# LTC-MTC_Filtering.net
KiCad netlist of a schematic drawn in Altium Designer
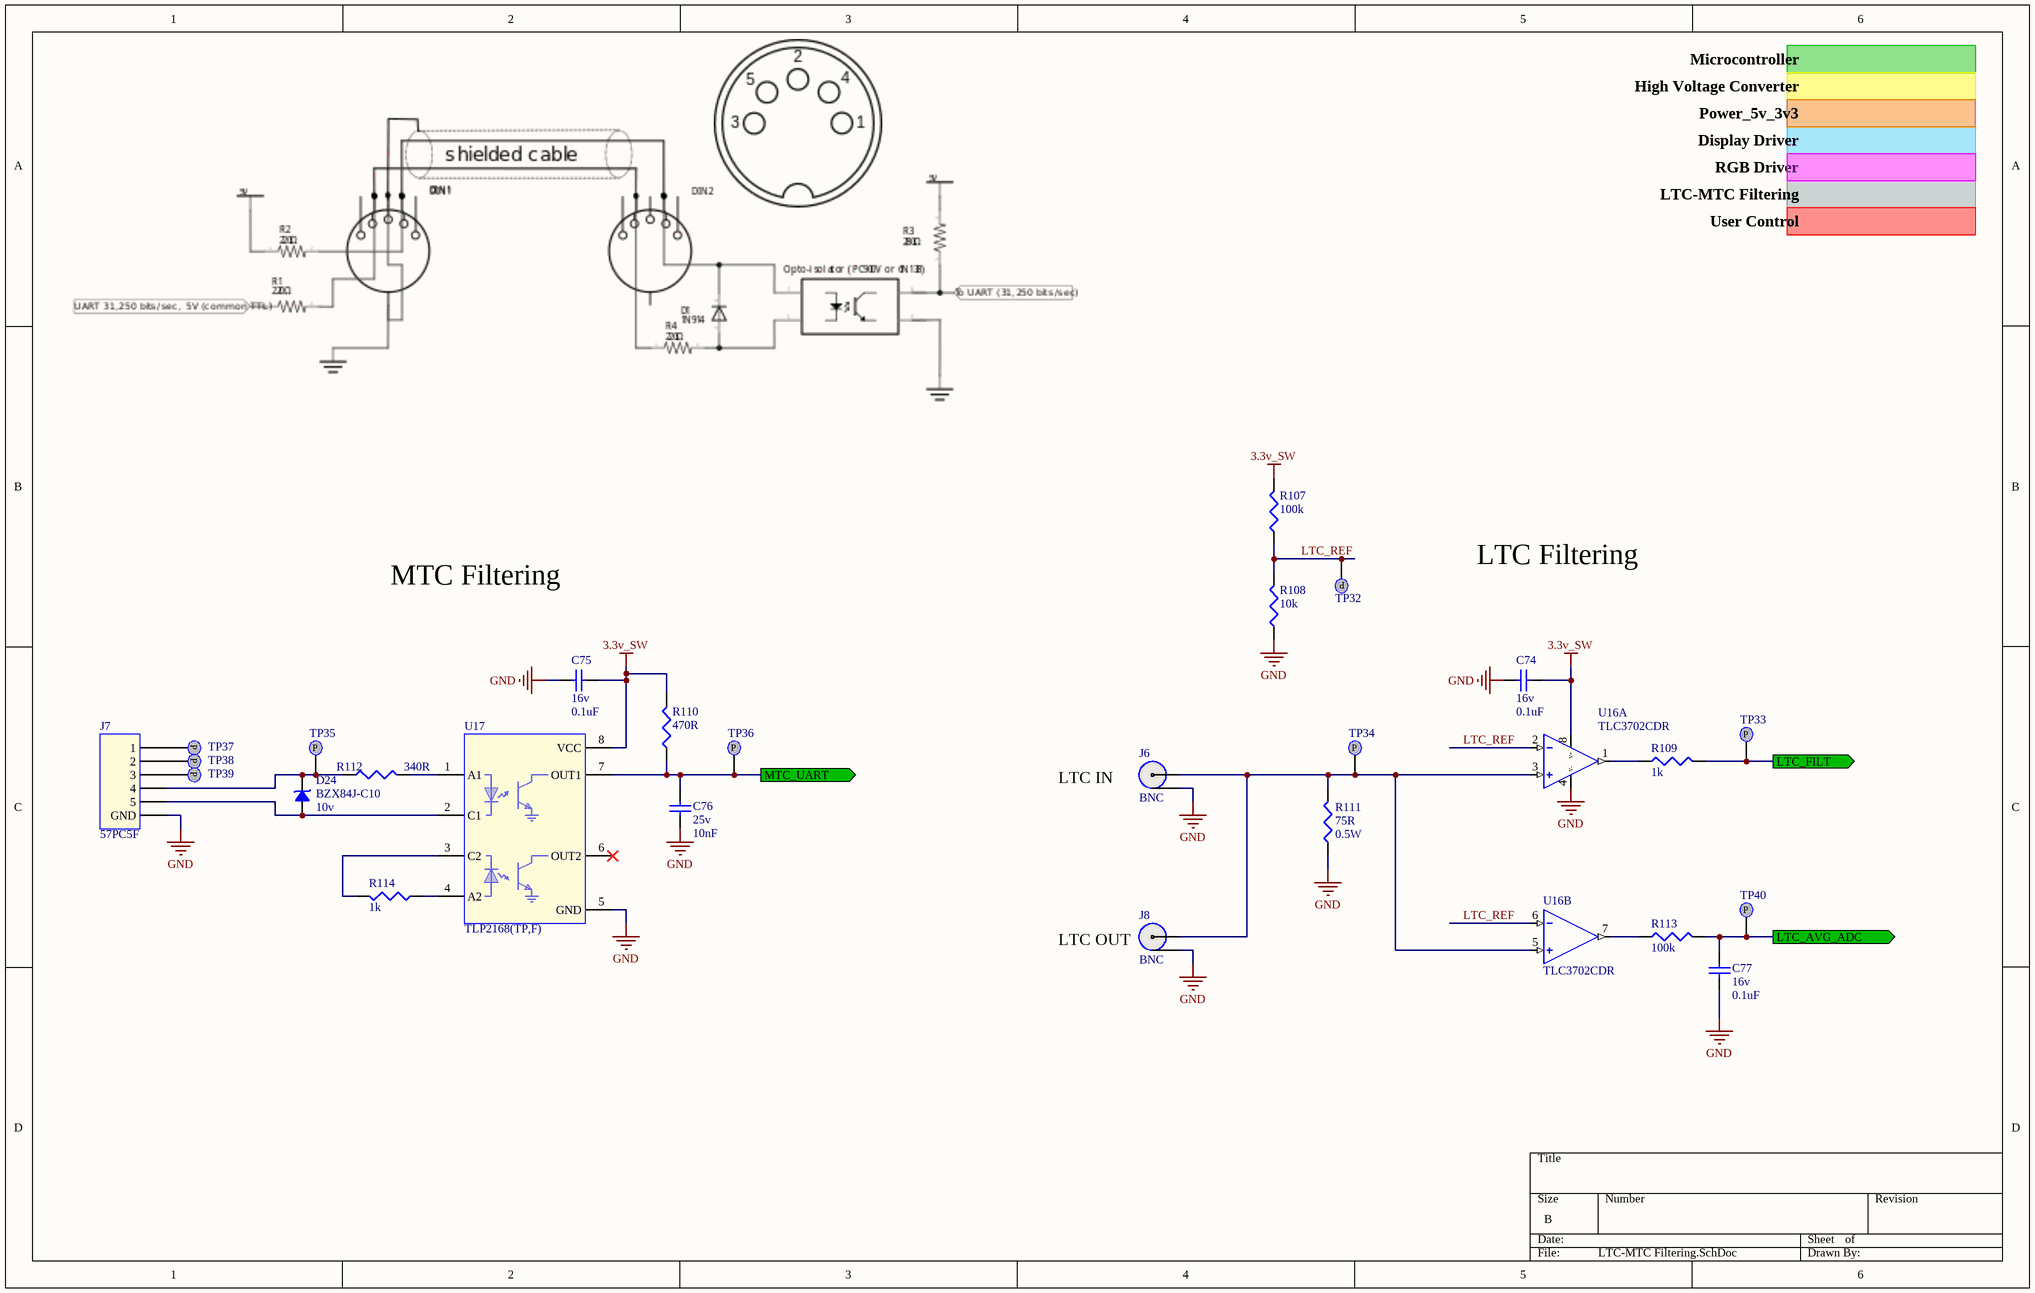
[diagram p0: LTC-MTC Filtering.SchDoc]

(export (version "E")
  (design (tool "Eeschema 10.0.6"))
  (components
    (comp (ref "C74")
      (value "0.1uF")
      (footprint "CAP0603R")
      (fields (field (name "MFG") "Vishay") (field (name "VOLTAGE") "16v"))
      (libsource (lib "Altium Library") (part "0.1uF 16v (0603)"))
    )
    (comp (ref "C75")
      (value "0.1uF")
      (footprint "CAP0603R")
      (fields (field (name "MFG") "Vishay") (field (name "VOLTAGE") "16v"))
      (libsource (lib "Altium Library") (part "0.1uF 16v (0603)"))
    )
    (comp (ref "C76")
      (value "10nF")
      (footprint "CAP0402R")
      (fields (field (name "TOLERANCE") "5%") (field (name "MFG") "Vishay") (field (name "VOLTAGE") "25v"))
      (libsource (lib "Altium Library") (part "10nF 25v (0402)"))
    )
    (comp (ref "C77")
      (value "0.1uF")
      (footprint "CAP0603R")
      (fields (field (name "MFG") "Vishay") (field (name "VOLTAGE") "16v"))
      (libsource (lib "Altium Library") (part "0.1uF 16v (0603)"))
    )
    (comp (ref "D24")
      (value "BZX84J-C10")
      (footprint "SOD-323 (SC-90)")
      (description "Zener, 10v, Single")
      (fields (field (name "MFG") "NXP") (field (name "OPER_VOLTAGE") "10v"))
      (libsource (lib "Altium Library") (part "BZX84J-C10"))
    )
    (comp (ref "J6")
      (value "BNC")
      (footprint "BNC Connector")
      (fields (field (name "MFG") "VITELEC"))
      (libsource (lib "Altium Library") (part "BNC Connector"))
    )
    (comp (ref "J7")
      (value "57PC5F")
      (footprint "57PC5F")
      (description "5-pin DIN Connector")
      (fields (field (name "MFG") "SWITCHCRAFT"))
      (libsource (lib "Altium Library") (part "57PC5F"))
    )
    (comp (ref "J8")
      (value "BNC")
      (footprint "BNC Connector")
      (fields (field (name "MFG") "VITELEC"))
      (libsource (lib "Altium Library") (part "BNC Connector"))
    )
    (comp (ref "R107")
      (value "100k")
      (footprint "RES0402R")
      (fields (field (name "TOLERANCE") "1%") (field (name "POWER") "63mW") (field (name "MFG") "Vishay"))
      (libsource (lib "Altium Library") (part "100k (0402)"))
    )
    (comp (ref "R108")
      (value "10k")
      (footprint "RES0402R")
      (fields (field (name "TOLERANCE") "1%") (field (name "POWER") "63mW") (field (name "MFG") "Vishay"))
      (libsource (lib "Altium Library") (part "10k (0402)"))
    )
    (comp (ref "R109")
      (value "1k")
      (footprint "RES0402R")
      (fields (field (name "TOLERANCE") "1%") (field (name "POWER") "63mW") (field (name "MFG") "Vishay"))
      (libsource (lib "Altium Library") (part "1k (0402)"))
    )
    (comp (ref "R110")
      (value "470R")
      (footprint "RES0603R")
      (fields (field (name "TOLERANCE") "1%") (field (name "POWER") "0.1W") (field (name "MFG") "Vishay"))
      (libsource (lib "Altium Library") (part "470R (0603)"))
    )
    (comp (ref "R111")
      (value "75R")
      (footprint "RES1210R")
      (fields (field (name "TOLERANCE") "1%") (field (name "POWER") "0.5W") (field (name "MFG") "Vishay"))
      (libsource (lib "Altium Library") (part "75R (1210)"))
    )
    (comp (ref "R112")
      (value "340R")
      (footprint "RES0603R")
      (fields (field (name "TOLERANCE") "1%") (field (name "POWER") "0.1W") (field (name "MFG") "Vishay"))
      (libsource (lib "Altium Library") (part "340R (0603)"))
    )
    (comp (ref "R113")
      (value "100k")
      (footprint "RES0402R")
      (fields (field (name "TOLERANCE") "1%") (field (name "POWER") "63mW") (field (name "MFG") "Vishay"))
      (libsource (lib "Altium Library") (part "100k (0402)"))
    )
    (comp (ref "R114")
      (value "1k")
      (footprint "RES0402R")
      (fields (field (name "TOLERANCE") "1%") (field (name "POWER") "63mW") (field (name "MFG") "Vishay"))
      (libsource (lib "Altium Library") (part "1k (0402)"))
    )
    (comp (ref "TP32")
      (value "NONE")
      (footprint "TESTPOINT - 1.5mm Round Pad")
      (description "1.5mm Testpoint")
      (libsource (lib "Altium Library") (part "Testpoint 1.5mm Pad"))
    )
    (comp (ref "TP33")
      (value "NONE")
      (footprint "TESTPOINT - 1.5mm Round Pad")
      (description "1.5mm Testpoint")
      (libsource (lib "Altium Library") (part "Testpoint 1.5mm Pad"))
    )
    (comp (ref "TP34")
      (value "NONE")
      (footprint "TESTPOINT - 1.5mm Round Pad")
      (description "1.5mm Testpoint")
      (libsource (lib "Altium Library") (part "Testpoint 1.5mm Pad"))
    )
    (comp (ref "TP35")
      (value "NONE")
      (footprint "TESTPOINT - 1.5mm Round Pad")
      (description "1.5mm Testpoint")
      (libsource (lib "Altium Library") (part "Testpoint 1.5mm Pad"))
    )
    (comp (ref "TP36")
      (value "NONE")
      (footprint "TESTPOINT - 1.5mm Round Pad")
      (description "1.5mm Testpoint")
      (libsource (lib "Altium Library") (part "Testpoint 1.5mm Pad"))
    )
    (comp (ref "TP37")
      (value "NONE")
      (footprint "TESTPOINT - 1.5mm Round Pad")
      (description "1.5mm Testpoint")
      (libsource (lib "Altium Library") (part "Testpoint 1.5mm Pad"))
    )
    (comp (ref "TP38")
      (value "NONE")
      (footprint "TESTPOINT - 1.5mm Round Pad")
      (description "1.5mm Testpoint")
      (libsource (lib "Altium Library") (part "Testpoint 1.5mm Pad"))
    )
    (comp (ref "TP39")
      (value "NONE")
      (footprint "TESTPOINT - 1.5mm Round Pad")
      (description "1.5mm Testpoint")
      (libsource (lib "Altium Library") (part "Testpoint 1.5mm Pad"))
    )
    (comp (ref "TP40")
      (value "NONE")
      (footprint "TESTPOINT - 1.5mm Round Pad")
      (description "1.5mm Testpoint")
      (libsource (lib "Altium Library") (part "Testpoint 1.5mm Pad"))
    )
    (comp (ref "U16")
      (value "TLC3702CDR")
      (footprint "SOIC-8")
      (description "Comparator, Dual, Push-Pull")
      (fields (field (name "MFG") "TI"))
      (libsource (lib "Altium Library") (part "TLC3702CDR"))
    )
    (comp (ref "U17")
      (value "TLP2168(TP,F)")
      (footprint "SOIC-8")
      (description "Optocoupler, Dual, 10MBPS")
      (fields (field (name "MFG") "TOSHIBA"))
      (libsource (lib "Altium Library") (part "TLP2168(TP,F)"))
    )
  )
  (nets
    (net (code "1") (name "/LTC_AVG_ADC") (class "Default")
      (node (ref "C77") (pin "1") (pinfunction "1_1") (pintype "passive"))
      (node (ref "R113") (pin "2") (pinfunction "2_2") (pintype "passive"))
      (node (ref "TP40") (pin "1") (pinfunction "1_1") (pintype "passive"))
    )
    (net (code "2") (name "/LTC_FILT") (class "Default")
      (node (ref "R109") (pin "2") (pinfunction "2_2") (pintype "passive"))
      (node (ref "TP33") (pin "1") (pinfunction "1_1") (pintype "passive"))
    )
    (net (code "3") (name "/LTC_REF") (class "Default")
      (node (ref "R107") (pin "1") (pinfunction "1_1") (pintype "passive"))
      (node (ref "R108") (pin "2") (pinfunction "2_2") (pintype "passive"))
      (node (ref "TP32") (pin "1") (pinfunction "1_1") (pintype "passive"))
      (node (ref "U16") (pin "2") (pinfunction "-IN_A_2") (pintype "input"))
      (node (ref "U16") (pin "6") (pinfunction "-IN_B_6") (pintype "input"))
    )
    (net (code "4") (name "/MTC_UART") (class "Default")
      (node (ref "C76") (pin "1") (pinfunction "1_1") (pintype "passive"))
      (node (ref "R110") (pin "1") (pinfunction "1_1") (pintype "passive"))
      (node (ref "TP36") (pin "1") (pinfunction "1_1") (pintype "passive"))
      (node (ref "U17") (pin "7") (pinfunction "OUT1_7") (pintype "passive"))
    )
    (net (code "5") (name "3.3v_SW") (class "Default")
      (node (ref "C74") (pin "2") (pinfunction "2_2") (pintype "passive"))
      (node (ref "C75") (pin "2") (pinfunction "2_2") (pintype "passive"))
      (node (ref "R107") (pin "2") (pinfunction "2_2") (pintype "passive"))
      (node (ref "R110") (pin "2") (pinfunction "2_2") (pintype "passive"))
      (node (ref "U16") (pin "8") (pinfunction "V+_8") (pintype "power_in"))
      (node (ref "U17") (pin "8") (pinfunction "VCC_8") (pintype "passive"))
    )
    (net (code "6") (name "GND") (class "Default")
      (node (ref "C74") (pin "1") (pinfunction "1_1") (pintype "passive"))
      (node (ref "C75") (pin "1") (pinfunction "1_1") (pintype "passive"))
      (node (ref "C76") (pin "2") (pinfunction "2_2") (pintype "passive"))
      (node (ref "C77") (pin "2") (pinfunction "2_2") (pintype "passive"))
      (node (ref "J6") (pin "2") (pinfunction "2_2") (pintype "passive"))
      (node (ref "J7") (pin "6") (pinfunction "GND_6") (pintype "passive"))
      (node (ref "J8") (pin "2") (pinfunction "2_2") (pintype "passive"))
      (node (ref "R108") (pin "1") (pinfunction "1_1") (pintype "passive"))
      (node (ref "R111") (pin "1") (pinfunction "1_1") (pintype "passive"))
      (node (ref "U16") (pin "4") (pinfunction "V-_4") (pintype "power_in"))
      (node (ref "U17") (pin "5") (pinfunction "GND_5") (pintype "passive"))
    )
    (net (code "7") (name "Net-(D24-A)") (class "Default")
      (node (ref "D24") (pin "2") (pinfunction "A_2") (pintype "passive"))
      (node (ref "J7") (pin "5") (pinfunction "5_5") (pintype "passive"))
      (node (ref "U17") (pin "2") (pinfunction "C1_2") (pintype "passive"))
    )
    (net (code "8") (name "Net-(D24-K)") (class "Default")
      (node (ref "D24") (pin "1") (pinfunction "K_1") (pintype "passive"))
      (node (ref "J7") (pin "4") (pinfunction "4_4") (pintype "passive"))
      (node (ref "R112") (pin "1") (pinfunction "1_1") (pintype "passive"))
      (node (ref "TP35") (pin "1") (pinfunction "1_1") (pintype "passive"))
    )
    (net (code "9") (name "Net-(J7-Pad1)") (class "Default")
      (node (ref "J7") (pin "1") (pinfunction "1_1") (pintype "passive"))
      (node (ref "TP37") (pin "1") (pinfunction "1_1") (pintype "passive"))
    )
    (net (code "10") (name "Net-(J7-Pad2)") (class "Default")
      (node (ref "J7") (pin "2") (pinfunction "2_2") (pintype "passive"))
      (node (ref "TP38") (pin "1") (pinfunction "1_1") (pintype "passive"))
    )
    (net (code "11") (name "Net-(J7-Pad3)") (class "Default")
      (node (ref "J7") (pin "3") (pinfunction "3_3") (pintype "passive"))
      (node (ref "TP39") (pin "1") (pinfunction "1_1") (pintype "passive"))
    )
    (net (code "12") (name "Net-(U16A-+IN_A)") (class "Default")
      (node (ref "J6") (pin "1") (pinfunction "1_1") (pintype "passive"))
      (node (ref "J8") (pin "1") (pinfunction "1_1") (pintype "passive"))
      (node (ref "R111") (pin "2") (pinfunction "2_2") (pintype "passive"))
      (node (ref "TP34") (pin "1") (pinfunction "1_1") (pintype "passive"))
      (node (ref "U16") (pin "3") (pinfunction "+IN_A_3") (pintype "input"))
      (node (ref "U16") (pin "5") (pinfunction "+IN_B_5") (pintype "input"))
    )
    (net (code "13") (name "Net-(U16A-OUT_A)") (class "Default")
      (node (ref "R109") (pin "1") (pinfunction "1_1") (pintype "passive"))
      (node (ref "U16") (pin "1") (pinfunction "OUT_A_1") (pintype "output"))
    )
    (net (code "14") (name "Net-(U16B-OUT_B)") (class "Default")
      (node (ref "R113") (pin "1") (pinfunction "1_1") (pintype "passive"))
      (node (ref "U16") (pin "7") (pinfunction "OUT_B_7") (pintype "output"))
    )
    (net (code "15") (name "Net-(U17-A1)") (class "Default")
      (node (ref "R112") (pin "2") (pinfunction "2_2") (pintype "passive"))
      (node (ref "U17") (pin "1") (pinfunction "A1_1") (pintype "passive"))
    )
    (net (code "16") (name "Net-(U17-A2)") (class "Default")
      (node (ref "R114") (pin "1") (pinfunction "1_1") (pintype "passive"))
      (node (ref "U17") (pin "4") (pinfunction "A2_4") (pintype "passive"))
    )
    (net (code "17") (name "Net-(U17-C2)") (class "Default")
      (node (ref "R114") (pin "2") (pinfunction "2_2") (pintype "passive"))
      (node (ref "U17") (pin "3") (pinfunction "C2_3") (pintype "passive"))
    )
    (net (code "18") (name "unconnected-(U17-OUT2-Pad6)") (class "Default")
      (node (ref "U17") (pin "6") (pinfunction "OUT2_6") (pintype "passive+no_connect"))
    )
  )
)
